# PCB.net
KiCad netlist of a schematic drawn in EAGLE
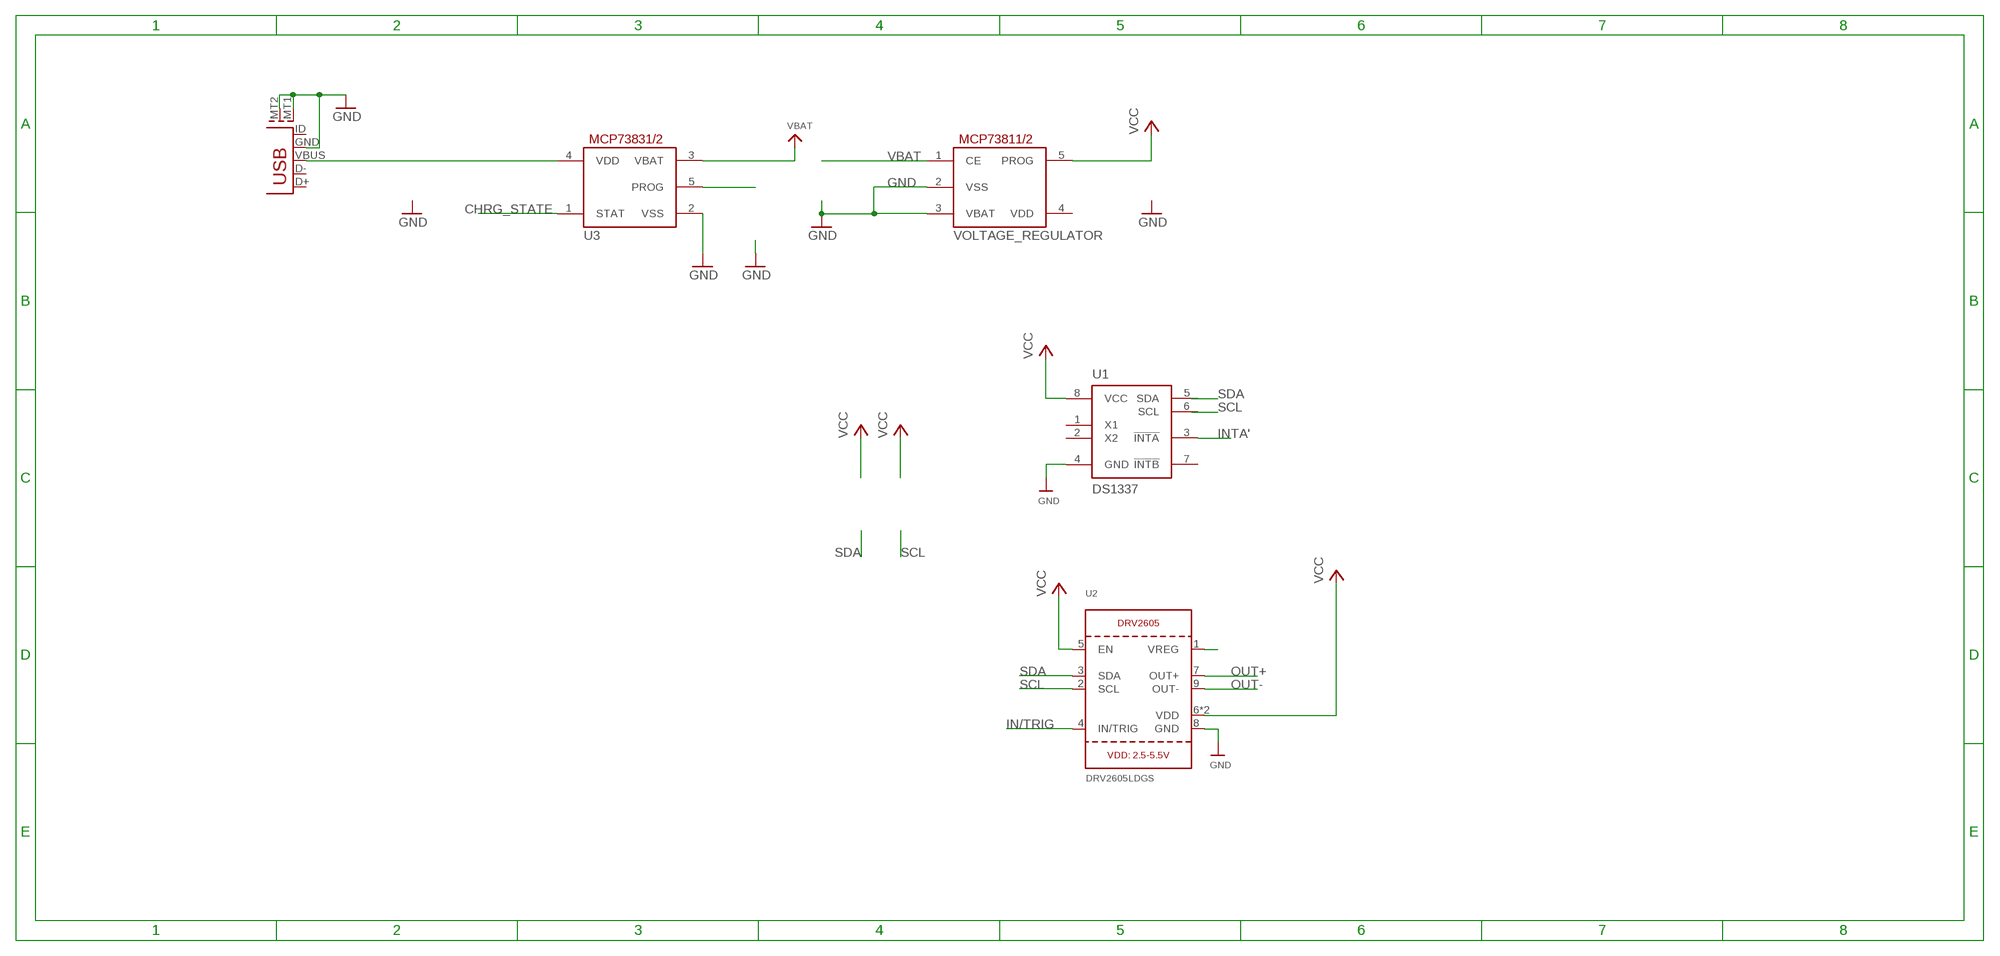
[diagram p0: schematic, sheet 1]

(export (version "E")
  (design (tool "Eeschema 10.0.6"))
  (components
    (comp (ref "U1")
      (value "DS1337")
      (footprint "eagle-import:UMAX8")
      (libsource (lib "eagle-import") (part "DS1337"))
    )
    (comp (ref "U2")
      (value "DRV2605LDGS")
      (footprint "eagle-import:PSOP10")
      (libsource (lib "eagle-import") (part "DRV2605_SOP"))
    )
    (comp (ref "U3")
      (value "MCP73832T-2ACI/OT")
      (footprint "eagle-import:SOT23-5L")
      (libsource (lib "eagle-import") (part "MCP73831/OT"))
    )
    (comp (ref "USB1")
      (value "USB-MICROBLARGEPAD")
      (footprint "eagle-import:USB-MICROB_LARGEPAD")
      (libsource (lib "eagle-import") (part "USB-MICROBLARGEPAD"))
    )
    (comp (ref "VOLTAGE_REGULATOR")
      (value "MCP73811/2")
      (footprint "eagle-import:SOT23-5L")
      (libsource (lib "eagle-import") (part "MCP73811/2"))
    )
  )
  (nets
    (net (code "1") (name "/CHRG_STATE") (class "Default")
      (node (ref "U3") (pin "1") (pinfunction "STAT_1") (pintype "output"))
    )
    (net (code "2") (name "/INTA'") (class "Default")
      (node (ref "U1") (pin "3") (pinfunction "~{INTA}_3") (pintype "bidirectional"))
    )
    (net (code "3") (name "/IN{slash}TRIG") (class "Default")
      (node (ref "U2") (pin "4") (pinfunction "IN/TRIG_4") (pintype "input"))
    )
    (net (code "4") (name "/OUT+") (class "Default")
      (node (ref "U2") (pin "7") (pinfunction "OUT+_7") (pintype "output"))
    )
    (net (code "5") (name "/OUT-") (class "Default")
      (node (ref "U2") (pin "9") (pinfunction "OUT-_9") (pintype "output"))
    )
    (net (code "6") (name "/SCL") (class "Default")
      (node (ref "U2") (pin "2") (pinfunction "SCL_2") (pintype "input"))
    )
    (net (code "7") (name "/SDA") (class "Default")
      (node (ref "U2") (pin "3") (pinfunction "SDA_3") (pintype "bidirectional"))
    )
    (net (code "8") (name "/VDD") (class "Default")
      (node (ref "VOLTAGE_REGULATOR") (pin "4") (pinfunction "VDD_4") (pintype "power_in"))
    )
    (net (code "9") (name "GND") (class "Default")
      (node (ref "U1") (pin "4") (pinfunction "GND_4") (pintype "bidirectional"))
      (node (ref "U2") (pin "8") (pinfunction "GND_8") (pintype "power_in"))
      (node (ref "U3") (pin "2") (pinfunction "VSS_2") (pintype "power_in"))
      (node (ref "USB1") (pin "GND") (pinfunction "GND_GND") (pintype "bidirectional"))
      (node (ref "USB1") (pin "MT1") (pinfunction "SHEILD1_MT1") (pintype "bidirectional"))
      (node (ref "USB1") (pin "MT2") (pinfunction "SHEILD2_MT2") (pintype "bidirectional"))
      (node (ref "VOLTAGE_REGULATOR") (pin "2") (pinfunction "VSS_2") (pintype "power_in"))
      (node (ref "VOLTAGE_REGULATOR") (pin "3") (pinfunction "VBAT_3") (pintype "bidirectional"))
    )
    (net (code "10") (name "Net-(U3-VDD)") (class "Default")
      (node (ref "U3") (pin "4") (pinfunction "VDD_4") (pintype "power_in"))
      (node (ref "USB1") (pin "VBUS") (pinfunction "VBUS_VBUS") (pintype "bidirectional"))
    )
    (net (code "11") (name "VBAT") (class "Default")
      (node (ref "U3") (pin "3") (pinfunction "VBAT_3") (pintype "bidirectional"))
      (node (ref "VOLTAGE_REGULATOR") (pin "1") (pinfunction "CE_1") (pintype "input"))
    )
    (net (code "12") (name "VCC") (class "Default")
      (node (ref "U1") (pin "8") (pinfunction "VCC_8") (pintype "bidirectional"))
      (node (ref "U2") (pin "10") (pinfunction "VDD_10") (pintype "power_in"))
      (node (ref "U2") (pin "5") (pinfunction "EN_5") (pintype "input"))
      (node (ref "U2") (pin "6") (pinfunction "VDD_6") (pintype "power_in"))
      (node (ref "VOLTAGE_REGULATOR") (pin "5") (pinfunction "PROG_5") (pintype "input"))
    )
    (net (code "13") (name "unconnected-(U1-SCL-Pad6)") (class "Default")
      (node (ref "U1") (pin "6") (pinfunction "SCL_6") (pintype "bidirectional"))
    )
    (net (code "14") (name "unconnected-(U1-SDA-Pad5)") (class "Default")
      (node (ref "U1") (pin "5") (pinfunction "SDA_5") (pintype "bidirectional"))
    )
    (net (code "15") (name "unconnected-(U1-X1-Pad1)") (class "Default")
      (node (ref "U1") (pin "1") (pinfunction "X1_1") (pintype "bidirectional"))
    )
    (net (code "16") (name "unconnected-(U1-X2-Pad2)") (class "Default")
      (node (ref "U1") (pin "2") (pinfunction "X2_2") (pintype "bidirectional"))
    )
    (net (code "17") (name "unconnected-(U1-~{INTB}-Pad7)") (class "Default")
      (node (ref "U1") (pin "7") (pinfunction "~{INTB}_7") (pintype "bidirectional"))
    )
    (net (code "18") (name "unconnected-(U2-VREG-Pad1)") (class "Default")
      (node (ref "U2") (pin "1") (pinfunction "VREG_1") (pintype "output"))
    )
    (net (code "19") (name "unconnected-(U3-PROG-Pad5)") (class "Default")
      (node (ref "U3") (pin "5") (pinfunction "PROG_5") (pintype "input"))
    )
    (net (code "20") (name "unconnected-(USB1-PadD+)") (class "Default")
      (node (ref "USB1") (pin "D+") (pinfunction "D+_D+") (pintype "bidirectional"))
    )
    (net (code "21") (name "unconnected-(USB1-PadD-)") (class "Default")
      (node (ref "USB1") (pin "D-") (pinfunction "D-_D-") (pintype "bidirectional"))
    )
    (net (code "22") (name "unconnected-(USB1-PadID)") (class "Default")
      (node (ref "USB1") (pin "ID") (pinfunction "ID_ID") (pintype "bidirectional"))
    )
  )
)
